# MCU.net
KiCad netlist of a schematic drawn in Altium Designer
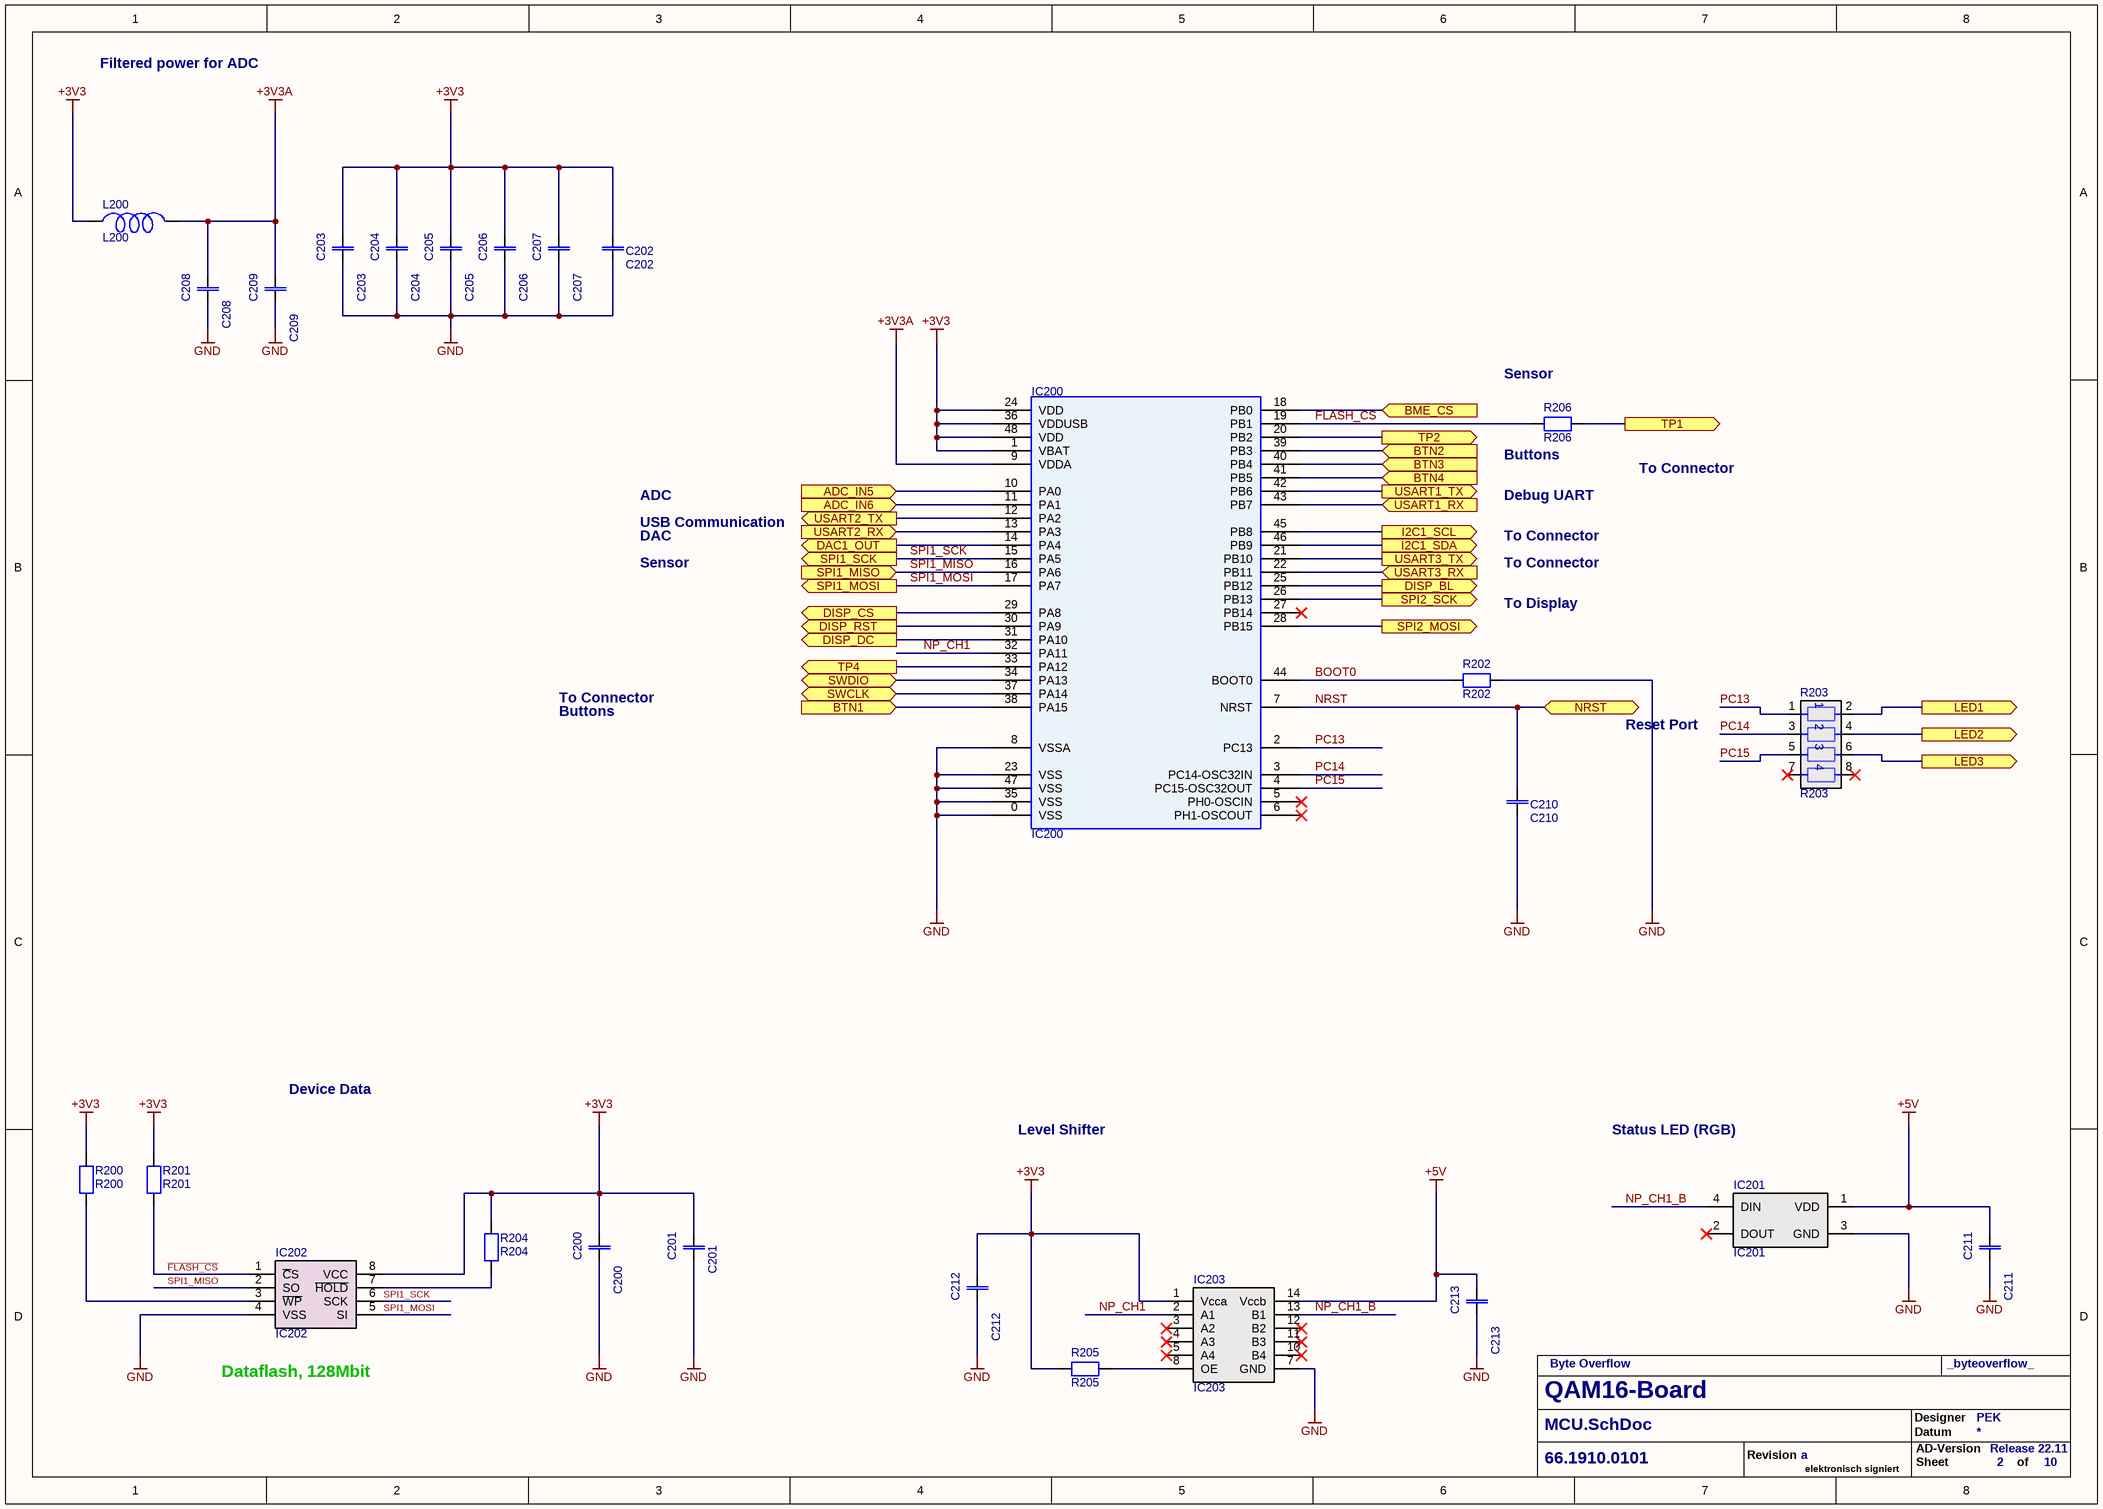
[diagram p0: MCU.SchDoc]

(export (version "E")
  (design (tool "Eeschema 10.0.6"))
  (components
    (comp (ref "C200")
      (value "C 100nF 50V X7R")
      (footprint "0603-1608")
      (description "Capacitor")
      (fields
        (field (name "MANUFACTURER") "KEMET")
        (field (name "MANUFACTURER PART NUMBER") "C0603C104K5RACTU")
      )
      (libsource (lib "Database_Libs1") (part "Kondensator"))
    )
    (comp (ref "C201")
      (value "C 1uF 50V")
      (footprint "0805-2012")
      (description "Capacitor")
      (fields
        (field (name "MANUFACTURER") "Murata Electronics North America")
        (field (name "MANUFACTURER PART NUMBER") "GRM21BF51H105ZA12L")
      )
      (libsource (lib "Database_Libs1") (part "Kondensator"))
    )
    (comp (ref "C202")
      (value "C 4.7uF 25V")
      (footprint "0603-1608")
      (description "Capacitor")
      (fields
        (field (name "MANUFACTURER") "Murata Electronics North America")
        (field (name "MANUFACTURER PART NUMBER") "GRM188R61E475ME11D")
      )
      (libsource (lib "Database_Libs1") (part "Kondensator"))
    )
    (comp (ref "C203")
      (value "C 100nF 50V X7R")
      (footprint "0603-1608")
      (description "Capacitor")
      (fields
        (field (name "MANUFACTURER") "KEMET")
        (field (name "MANUFACTURER PART NUMBER") "C0603C104K5RACTU")
      )
      (libsource (lib "Database_Libs1") (part "Kondensator"))
    )
    (comp (ref "C204")
      (value "C 100nF 50V X7R")
      (footprint "0603-1608")
      (description "Capacitor")
      (fields
        (field (name "MANUFACTURER") "KEMET")
        (field (name "MANUFACTURER PART NUMBER") "C0603C104K5RACTU")
      )
      (libsource (lib "Database_Libs1") (part "Kondensator"))
    )
    (comp (ref "C205")
      (value "C 100nF 50V X7R")
      (footprint "0603-1608")
      (description "Capacitor")
      (fields
        (field (name "MANUFACTURER") "KEMET")
        (field (name "MANUFACTURER PART NUMBER") "C0603C104K5RACTU")
      )
      (libsource (lib "Database_Libs1") (part "Kondensator"))
    )
    (comp (ref "C206")
      (value "C 100nF 50V X7R")
      (footprint "0603-1608")
      (description "Capacitor")
      (fields
        (field (name "MANUFACTURER") "KEMET")
        (field (name "MANUFACTURER PART NUMBER") "C0603C104K5RACTU")
      )
      (libsource (lib "Database_Libs1") (part "Kondensator"))
    )
    (comp (ref "C207")
      (value "C 100nF 50V X7R")
      (footprint "0603-1608")
      (description "Capacitor")
      (fields
        (field (name "MANUFACTURER") "KEMET")
        (field (name "MANUFACTURER PART NUMBER") "C0603C104K5RACTU")
      )
      (libsource (lib "Database_Libs1") (part "Kondensator"))
    )
    (comp (ref "C208")
      (value "C 1uF 50V")
      (footprint "0805-2012")
      (description "Capacitor")
      (fields
        (field (name "MANUFACTURER") "Murata Electronics North America")
        (field (name "MANUFACTURER PART NUMBER") "GRM21BF51H105ZA12L")
      )
      (libsource (lib "Database_Libs1") (part "Kondensator"))
    )
    (comp (ref "C209")
      (value "C 100nF 50V X7R")
      (footprint "0603-1608")
      (description "Capacitor")
      (fields
        (field (name "MANUFACTURER") "KEMET")
        (field (name "MANUFACTURER PART NUMBER") "C0603C104K5RACTU")
      )
      (libsource (lib "Database_Libs1") (part "Kondensator"))
    )
    (comp (ref "C210")
      (value "C 100nF 50V X7R")
      (footprint "0603-1608")
      (description "Capacitor")
      (fields
        (field (name "MANUFACTURER") "KEMET")
        (field (name "MANUFACTURER PART NUMBER") "C0603C104K5RACTU")
      )
      (libsource (lib "Database_Libs1") (part "Kondensator"))
    )
    (comp (ref "C211")
      (value "C 100nF 50V X7R")
      (footprint "0603-1608")
      (description "Capacitor")
      (fields
        (field (name "MANUFACTURER") "KEMET")
        (field (name "MANUFACTURER PART NUMBER") "C0603C104K5RACTU")
      )
      (libsource (lib "Database_Libs1") (part "Kondensator"))
    )
    (comp (ref "C212")
      (value "C 100nF 50V X7R")
      (footprint "0603-1608")
      (description "Capacitor")
      (fields
        (field (name "MANUFACTURER") "KEMET")
        (field (name "MANUFACTURER PART NUMBER") "C0603C104K5RACTU")
      )
      (libsource (lib "Database_Libs1") (part "Kondensator"))
    )
    (comp (ref "C213")
      (value "C 100nF 50V X7R")
      (footprint "0603-1608")
      (description "Capacitor")
      (fields
        (field (name "MANUFACTURER") "KEMET")
        (field (name "MANUFACTURER PART NUMBER") "C0603C104K5RACTU")
      )
      (libsource (lib "Database_Libs1") (part "Kondensator"))
    )
    (comp (ref "IC200")
      (value "ST STM32L452CEU6")
      (footprint "QFN48 7x7x0.9 WIZnet")
      (description "uC")
      (fields
        (field (name "MANUFACTURER") "STMicroelectronics")
        (field (name "MANUFACTURER PART NUMBER") "STM32L452CEU6")
      )
      (libsource (lib "Database_Libs1") (part "STM32L452CEU6"))
    )
    (comp (ref "IC201")
      (value "WS2812B")
      (footprint "LED_2812")
      (description "LED")
      (fields (field (name "MANUFACTURER") "China") (field (name "VERIFICATION") "14.11.2019 PEK"))
      (libsource (lib "Database_Libs1") (part "WS2812B"))
    )
    (comp (ref "IC202")
      (value "AT25M01-SHM-T")
      (footprint "SOIC-8")
      (description "Memory")
      (fields (field (name "MANUFACTURER") "Microchip Technology"))
      (libsource (lib "Database_Libs1") (part "Speicher SPI"))
    )
    (comp (ref "IC203")
      (value "TXB0104")
      (footprint "TSSOP14")
      (description "Level-shifter")
      (fields
        (field (name "MANUFACTURER") "Texas Instruments")
        (field (name "MANUFACTURER PART NUMBER") "TXB0104PWR")
      )
      (libsource (lib "Database_Libs1") (part "TXB0104"))
    )
    (comp (ref "L200")
      (value "L 22nH")
      (footprint "0603-1608")
      (description "Inductor")
      (fields
        (field (name "MANUFACTURER") "Taiyo Yuden")
        (field (name "MANUFACTURER PART NUMBER") "HK160822NJ-T")
        (field (name "VERIFICATION") "05.07.2012 OPT")
      )
      (libsource (lib "Database_Libs1") (part "Spule"))
    )
    (comp (ref "R200")
      (value "R 10k 1%")
      (footprint "0603-1608")
      (description "Resistor")
      (fields
        (field (name "MANUFACTURER") "Vishay Dale")
        (field (name "MANUFACTURER PART NUMBER") "CRCW060310K0FKEAHP")
        (field (name "VERIFICATION") "05.07.2012 OPT")
      )
      (libsource (lib "Database_Libs1") (part "Resistor"))
    )
    (comp (ref "R201")
      (value "R 10k 1%")
      (footprint "0603-1608")
      (description "Resistor")
      (fields
        (field (name "MANUFACTURER") "Vishay Dale")
        (field (name "MANUFACTURER PART NUMBER") "CRCW060310K0FKEAHP")
        (field (name "VERIFICATION") "05.07.2012 OPT")
      )
      (libsource (lib "Database_Libs1") (part "Resistor"))
    )
    (comp (ref "R202")
      (value "R 10k 1%")
      (footprint "0603-1608")
      (description "Resistor")
      (fields
        (field (name "MANUFACTURER") "Vishay Dale")
        (field (name "MANUFACTURER PART NUMBER") "CRCW060310K0FKEAHP")
        (field (name "VERIFICATION") "05.07.2012 OPT")
      )
      (libsource (lib "Database_Libs1") (part "Resistor"))
    )
    (comp (ref "R203")
      (value "R 100E 4x 5.0%")
      (footprint "Array-2010-4Way")
      (description "Resistor")
      (fields
        (field (name "MANUFACTURER") "Vishay Dale")
        (field (name "MANUFACTURER PART NUMBER") "CRA04S083100RJTD")
      )
      (libsource (lib "Database_Libs1") (part "Resistor 4x"))
    )
    (comp (ref "R204")
      (value "R 10k 1%")
      (footprint "0603-1608")
      (description "Resistor")
      (fields
        (field (name "MANUFACTURER") "Vishay Dale")
        (field (name "MANUFACTURER PART NUMBER") "CRCW060310K0FKEAHP")
        (field (name "VERIFICATION") "05.07.2012 OPT")
      )
      (libsource (lib "Database_Libs1") (part "Resistor"))
    )
    (comp (ref "R205")
      (value "R 0E 1%")
      (footprint "0805-2012")
      (description "Resistor")
      (fields
        (field (name "MANUFACTURER") "Vishay Dale")
        (field (name "MANUFACTURER PART NUMBER") "CRCW08050000Z0EAHP")
        (field (name "VERIFICATION") "05.03.2013 ENP")
      )
      (libsource (lib "Database_Libs1") (part "Resistor"))
    )
    (comp (ref "R206")
      (value "R 100E 1%")
      (footprint "0603-1608")
      (description "Resistor")
      (fields
        (field (name "MANUFACTURER") "Vishay Dale")
        (field (name "MANUFACTURER PART NUMBER") "CRCW0603100RFKEA")
        (field (name "VERIFICATION") "05.07.2012 OPT")
      )
      (libsource (lib "Database_Libs1") (part "Resistor"))
    )
  )
  (nets
    (net (code "1") (name "+3V3") (class "Default")
      (node (ref "C200") (pin "1") (pinfunction "1_1") (pintype "passive"))
      (node (ref "C201") (pin "1") (pinfunction "1_1") (pintype "passive"))
      (node (ref "C202") (pin "1") (pinfunction "1_1") (pintype "passive"))
      (node (ref "C203") (pin "1") (pinfunction "1_1") (pintype "passive"))
      (node (ref "C204") (pin "1") (pinfunction "1_1") (pintype "passive"))
      (node (ref "C205") (pin "1") (pinfunction "1_1") (pintype "passive"))
      (node (ref "C206") (pin "1") (pinfunction "1_1") (pintype "passive"))
      (node (ref "C207") (pin "1") (pinfunction "1_1") (pintype "passive"))
      (node (ref "C212") (pin "1") (pinfunction "1_1") (pintype "passive"))
      (node (ref "IC200") (pin "1") (pinfunction "VBAT_1") (pintype "passive"))
      (node (ref "IC200") (pin "24") (pinfunction "VDD_24") (pintype "passive"))
      (node (ref "IC200") (pin "36") (pinfunction "VDDUSB_36") (pintype "passive"))
      (node (ref "IC200") (pin "48") (pinfunction "VDD_48") (pintype "passive"))
      (node (ref "IC202") (pin "8") (pinfunction "VCC_8") (pintype "power_in"))
      (node (ref "IC203") (pin "1") (pinfunction "Vcca_1") (pintype "passive"))
      (node (ref "L200") (pin "1") (pintype "passive"))
      (node (ref "R200") (pin "2") (pinfunction "2_2") (pintype "passive"))
      (node (ref "R201") (pin "2") (pinfunction "2_2") (pintype "passive"))
      (node (ref "R204") (pin "2") (pinfunction "2_2") (pintype "passive"))
      (node (ref "R205") (pin "1") (pinfunction "1_1") (pintype "passive"))
    )
    (net (code "2") (name "+3V3A") (class "Default")
      (node (ref "C208") (pin "1") (pinfunction "1_1") (pintype "passive"))
      (node (ref "C209") (pin "1") (pinfunction "1_1") (pintype "passive"))
      (node (ref "IC200") (pin "9") (pinfunction "VDDA_9") (pintype "passive"))
      (node (ref "L200") (pin "2") (pintype "passive"))
    )
    (net (code "3") (name "+5V") (class "Default")
      (node (ref "C211") (pin "1") (pinfunction "1_1") (pintype "passive"))
      (node (ref "C213") (pin "1") (pinfunction "1_1") (pintype "passive"))
      (node (ref "IC201") (pin "1") (pinfunction "VDD_1") (pintype "passive"))
      (node (ref "IC203") (pin "14") (pinfunction "Vccb_14") (pintype "passive"))
    )
    (net (code "4") (name "/ADC_IN5") (class "Default")
      (node (ref "IC200") (pin "10") (pinfunction "PA0_10") (pintype "passive"))
    )
    (net (code "5") (name "/ADC_IN6") (class "Default")
      (node (ref "IC200") (pin "11") (pinfunction "PA1_11") (pintype "passive"))
    )
    (net (code "6") (name "/BME_CS") (class "Default")
      (node (ref "IC200") (pin "18") (pinfunction "PB0_18") (pintype "passive"))
    )
    (net (code "7") (name "/BOOT0") (class "Default")
      (node (ref "IC200") (pin "44") (pinfunction "BOOT0_44") (pintype "passive"))
      (node (ref "R202") (pin "1") (pinfunction "1_1") (pintype "passive"))
    )
    (net (code "8") (name "/BTN1") (class "Default")
      (node (ref "IC200") (pin "38") (pinfunction "PA15_38") (pintype "passive"))
    )
    (net (code "9") (name "/BTN2") (class "Default")
      (node (ref "IC200") (pin "39") (pinfunction "PB3_39") (pintype "passive"))
    )
    (net (code "10") (name "/BTN3") (class "Default")
      (node (ref "IC200") (pin "40") (pinfunction "PB4_40") (pintype "passive"))
    )
    (net (code "11") (name "/BTN4") (class "Default")
      (node (ref "IC200") (pin "41") (pinfunction "PB5_41") (pintype "passive"))
    )
    (net (code "12") (name "/DAC1_OUT") (class "Default")
      (node (ref "IC200") (pin "14") (pinfunction "PA4_14") (pintype "passive"))
    )
    (net (code "13") (name "/DISP_BL") (class "Default")
      (node (ref "IC200") (pin "25") (pinfunction "PB12_25") (pintype "passive"))
    )
    (net (code "14") (name "/DISP_CS") (class "Default")
      (node (ref "IC200") (pin "29") (pinfunction "PA8_29") (pintype "passive"))
    )
    (net (code "15") (name "/DISP_DC") (class "Default")
      (node (ref "IC200") (pin "31") (pinfunction "PA10_31") (pintype "passive"))
    )
    (net (code "16") (name "/DISP_RST") (class "Default")
      (node (ref "IC200") (pin "30") (pinfunction "PA9_30") (pintype "passive"))
    )
    (net (code "17") (name "/FLASH_CS") (class "Default")
      (node (ref "IC200") (pin "19") (pinfunction "PB1_19") (pintype "passive"))
      (node (ref "IC202") (pin "1") (pinfunction "~{C}S_1") (pintype "passive"))
      (node (ref "R201") (pin "1") (pinfunction "1_1") (pintype "passive"))
      (node (ref "R206") (pin "1") (pinfunction "1_1") (pintype "passive"))
    )
    (net (code "18") (name "/I2C1_SCL") (class "Default")
      (node (ref "IC200") (pin "45") (pinfunction "PB8_45") (pintype "passive"))
    )
    (net (code "19") (name "/I2C1_SDA") (class "Default")
      (node (ref "IC200") (pin "46") (pinfunction "PB9_46") (pintype "passive"))
    )
    (net (code "20") (name "/LED1") (class "Default")
      (node (ref "R203") (pin "2") (pinfunction "2_2") (pintype "passive"))
    )
    (net (code "21") (name "/LED2") (class "Default")
      (node (ref "R203") (pin "4") (pinfunction "4_4") (pintype "passive"))
    )
    (net (code "22") (name "/LED3") (class "Default")
      (node (ref "R203") (pin "6") (pinfunction "6_6") (pintype "passive"))
    )
    (net (code "23") (name "/NP_CH1") (class "Default")
      (node (ref "IC200") (pin "32") (pinfunction "PA11_32") (pintype "passive"))
      (node (ref "IC203") (pin "2") (pinfunction "A1_2") (pintype "passive"))
    )
    (net (code "24") (name "/NP_CH1_B") (class "Default")
      (node (ref "IC201") (pin "4") (pinfunction "DIN_4") (pintype "passive"))
      (node (ref "IC203") (pin "13") (pinfunction "B1_13") (pintype "passive"))
    )
    (net (code "25") (name "/NRST") (class "Default")
      (node (ref "C210") (pin "1") (pinfunction "1_1") (pintype "passive"))
      (node (ref "IC200") (pin "7") (pinfunction "NRST_7") (pintype "passive"))
    )
    (net (code "26") (name "/PC13") (class "Default")
      (node (ref "IC200") (pin "2") (pinfunction "PC13_2") (pintype "passive"))
      (node (ref "R203") (pin "1") (pinfunction "1_1") (pintype "passive"))
    )
    (net (code "27") (name "/PC14") (class "Default")
      (node (ref "IC200") (pin "3") (pinfunction "PC14-OSC32IN_3") (pintype "passive"))
      (node (ref "R203") (pin "3") (pinfunction "3_3") (pintype "passive"))
    )
    (net (code "28") (name "/PC15") (class "Default")
      (node (ref "IC200") (pin "4") (pinfunction "PC15-OSC32OUT_4") (pintype "passive"))
      (node (ref "R203") (pin "5") (pinfunction "5_5") (pintype "passive"))
    )
    (net (code "29") (name "/SPI1_MISO") (class "Default")
      (node (ref "IC200") (pin "16") (pinfunction "PA6_16") (pintype "passive"))
      (node (ref "IC202") (pin "2") (pinfunction "SO_2") (pintype "passive"))
    )
    (net (code "30") (name "/SPI1_MOSI") (class "Default")
      (node (ref "IC200") (pin "17") (pinfunction "PA7_17") (pintype "passive"))
      (node (ref "IC202") (pin "5") (pinfunction "SI_5") (pintype "passive"))
    )
    (net (code "31") (name "/SPI1_SCK") (class "Default")
      (node (ref "IC200") (pin "15") (pinfunction "PA5_15") (pintype "passive"))
      (node (ref "IC202") (pin "6") (pinfunction "SCK_6") (pintype "passive"))
    )
    (net (code "32") (name "/SPI2_MOSI") (class "Default")
      (node (ref "IC200") (pin "28") (pinfunction "PB15_28") (pintype "passive"))
    )
    (net (code "33") (name "/SPI2_SCK") (class "Default")
      (node (ref "IC200") (pin "26") (pinfunction "PB13_26") (pintype "passive"))
    )
    (net (code "34") (name "/SWCLK") (class "Default")
      (node (ref "IC200") (pin "37") (pinfunction "PA14_37") (pintype "passive"))
    )
    (net (code "35") (name "/SWDIO") (class "Default")
      (node (ref "IC200") (pin "34") (pinfunction "PA13_34") (pintype "passive"))
    )
    (net (code "36") (name "/TP1") (class "Default")
      (node (ref "R206") (pin "2") (pinfunction "2_2") (pintype "passive"))
    )
    (net (code "37") (name "/TP2") (class "Default")
      (node (ref "IC200") (pin "20") (pinfunction "PB2_20") (pintype "passive"))
    )
    (net (code "38") (name "/TP4") (class "Default")
      (node (ref "IC200") (pin "33") (pinfunction "PA12_33") (pintype "passive"))
    )
    (net (code "39") (name "/USART1_RX") (class "Default")
      (node (ref "IC200") (pin "43") (pinfunction "PB7_43") (pintype "passive"))
    )
    (net (code "40") (name "/USART1_TX") (class "Default")
      (node (ref "IC200") (pin "42") (pinfunction "PB6_42") (pintype "passive"))
    )
    (net (code "41") (name "/USART2_RX") (class "Default")
      (node (ref "IC200") (pin "13") (pinfunction "PA3_13") (pintype "passive"))
    )
    (net (code "42") (name "/USART2_TX") (class "Default")
      (node (ref "IC200") (pin "12") (pinfunction "PA2_12") (pintype "passive"))
    )
    (net (code "43") (name "/USART3_RX") (class "Default")
      (node (ref "IC200") (pin "22") (pinfunction "PB11_22") (pintype "passive"))
    )
    (net (code "44") (name "/USART3_TX") (class "Default")
      (node (ref "IC200") (pin "21") (pinfunction "PB10_21") (pintype "passive"))
    )
    (net (code "45") (name "GND") (class "Default")
      (node (ref "C200") (pin "2") (pinfunction "2_2") (pintype "passive"))
      (node (ref "C201") (pin "2") (pinfunction "2_2") (pintype "passive"))
      (node (ref "C202") (pin "2") (pinfunction "2_2") (pintype "passive"))
      (node (ref "C203") (pin "2") (pinfunction "2_2") (pintype "passive"))
      (node (ref "C204") (pin "2") (pinfunction "2_2") (pintype "passive"))
      (node (ref "C205") (pin "2") (pinfunction "2_2") (pintype "passive"))
      (node (ref "C206") (pin "2") (pinfunction "2_2") (pintype "passive"))
      (node (ref "C207") (pin "2") (pinfunction "2_2") (pintype "passive"))
      (node (ref "C208") (pin "2") (pinfunction "2_2") (pintype "passive"))
      (node (ref "C209") (pin "2") (pinfunction "2_2") (pintype "passive"))
      (node (ref "C210") (pin "2") (pinfunction "2_2") (pintype "passive"))
      (node (ref "C211") (pin "2") (pinfunction "2_2") (pintype "passive"))
      (node (ref "C212") (pin "2") (pinfunction "2_2") (pintype "passive"))
      (node (ref "C213") (pin "2") (pinfunction "2_2") (pintype "passive"))
      (node (ref "IC200") (pin "0") (pinfunction "VSS_0") (pintype "passive"))
      (node (ref "IC200") (pin "23") (pinfunction "VSS_23") (pintype "passive"))
      (node (ref "IC200") (pin "35") (pinfunction "VSS_35") (pintype "passive"))
      (node (ref "IC200") (pin "47") (pinfunction "VSS_47") (pintype "passive"))
      (node (ref "IC200") (pin "8") (pinfunction "VSSA_8") (pintype "passive"))
      (node (ref "IC201") (pin "3") (pinfunction "GND_3") (pintype "passive"))
      (node (ref "IC202") (pin "4") (pinfunction "VSS_4") (pintype "power_in"))
      (node (ref "IC203") (pin "7") (pinfunction "GND_7") (pintype "passive"))
      (node (ref "R202") (pin "2") (pinfunction "2_2") (pintype "passive"))
    )
    (net (code "46") (name "Net-(IC202-HOLD)") (class "Default")
      (node (ref "IC202") (pin "7") (pinfunction "HOLD_7") (pintype "passive"))
      (node (ref "R204") (pin "1") (pinfunction "1_1") (pintype "passive"))
    )
    (net (code "47") (name "Net-(IC202-WP)") (class "Default")
      (node (ref "IC202") (pin "3") (pinfunction "WP_3") (pintype "passive"))
      (node (ref "R200") (pin "1") (pinfunction "1_1") (pintype "passive"))
    )
    (net (code "48") (name "Net-(IC203-OE)") (class "Default")
      (node (ref "IC203") (pin "8") (pinfunction "OE_8") (pintype "passive"))
      (node (ref "R205") (pin "2") (pinfunction "2_2") (pintype "passive"))
    )
    (net (code "49") (name "unconnected-(IC200-PB14-Pad27)") (class "Default")
      (node (ref "IC200") (pin "27") (pinfunction "PB14_27") (pintype "passive+no_connect"))
    )
    (net (code "50") (name "unconnected-(IC200-PH0-OSCIN-Pad5)") (class "Default")
      (node (ref "IC200") (pin "5") (pinfunction "PH0-OSCIN_5") (pintype "passive+no_connect"))
    )
    (net (code "51") (name "unconnected-(IC200-PH1-OSCOUT-Pad6)") (class "Default")
      (node (ref "IC200") (pin "6") (pinfunction "PH1-OSCOUT_6") (pintype "passive+no_connect"))
    )
    (net (code "52") (name "unconnected-(IC201-DOUT-Pad2)") (class "Default")
      (node (ref "IC201") (pin "2") (pinfunction "DOUT_2") (pintype "passive+no_connect"))
    )
    (net (code "53") (name "unconnected-(IC203-A2-Pad3)") (class "Default")
      (node (ref "IC203") (pin "3") (pinfunction "A2_3") (pintype "passive+no_connect"))
    )
    (net (code "54") (name "unconnected-(IC203-A3-Pad4)") (class "Default")
      (node (ref "IC203") (pin "4") (pinfunction "A3_4") (pintype "passive+no_connect"))
    )
    (net (code "55") (name "unconnected-(IC203-A4-Pad5)") (class "Default")
      (node (ref "IC203") (pin "5") (pinfunction "A4_5") (pintype "passive+no_connect"))
    )
    (net (code "56") (name "unconnected-(IC203-B2-Pad12)") (class "Default")
      (node (ref "IC203") (pin "12") (pinfunction "B2_12") (pintype "passive+no_connect"))
    )
    (net (code "57") (name "unconnected-(IC203-B3-Pad11)") (class "Default")
      (node (ref "IC203") (pin "11") (pinfunction "B3_11") (pintype "passive+no_connect"))
    )
    (net (code "58") (name "unconnected-(IC203-B4-Pad10)") (class "Default")
      (node (ref "IC203") (pin "10") (pinfunction "B4_10") (pintype "passive+no_connect"))
    )
    (net (code "59") (name "unconnected-(IC203-NC-Pad6)") (class "Default")
      (node (ref "IC203") (pin "6") (pinfunction "NC_6") (pintype "passive"))
    )
    (net (code "60") (name "unconnected-(IC203-NC-Pad9)") (class "Default")
      (node (ref "IC203") (pin "9") (pinfunction "NC_9") (pintype "passive"))
    )
    (net (code "61") (name "unconnected-(R203-Pad7)") (class "Default")
      (node (ref "R203") (pin "7") (pinfunction "7_7") (pintype "passive+no_connect"))
    )
    (net (code "62") (name "unconnected-(R203-Pad8)") (class "Default")
      (node (ref "R203") (pin "8") (pinfunction "8_8") (pintype "passive+no_connect"))
    )
  )
)
